# ledboard.net
KiCad netlist of a schematic drawn in EAGLE
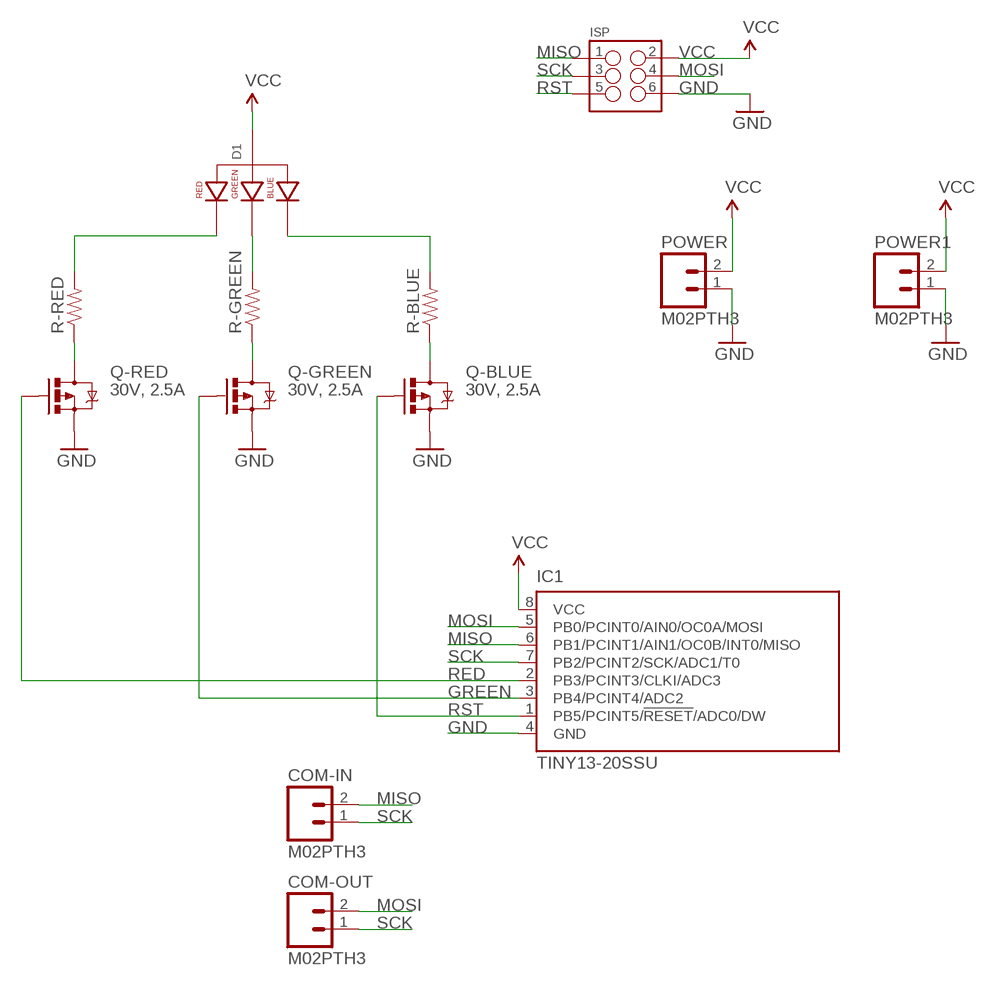
[diagram p0: schematic, sheet 1]

(export (version "E")
  (design (tool "Eeschema 10.0.6"))
  (components
    (comp (ref "COM-IN")
      (value "M02PTH3")
      (footprint "eagle-import:1X02_LONGPADS")
      (libsource (lib "eagle-import") (part "M02PTH3"))
    )
    (comp (ref "COM-OUT")
      (value "M02PTH3")
      (footprint "eagle-import:1X02_LONGPADS")
      (libsource (lib "eagle-import") (part "M02PTH3"))
    )
    (comp (ref "D1")
      (value "LED-RGB-CA-THRUCLEAR")
      (footprint "eagle-import:LED-RGB-THRU")
      (libsource (lib "eagle-import") (part "LED-RGB-CA-THRUCLEAR"))
    )
    (comp (ref "IC1")
      (value "TINY13-20SSU")
      (footprint "eagle-import:8S1")
      (fields (field (name "MPN") "ATTINY13-20SSU"))
      (libsource (lib "eagle-import") (part "TINY13SSU-20"))
    )
    (comp (ref "ISP")
      (value "M03X22X3_SILK_SM")
      (footprint "eagle-import:2X3")
      (libsource (lib "eagle-import") (part "M03X22X3_SILK_SM"))
    )
    (comp (ref "POWER")
      (value "M02PTH3")
      (footprint "eagle-import:1X02_LONGPADS")
      (libsource (lib "eagle-import") (part "M02PTH3"))
    )
    (comp (ref "POWER1")
      (value "M02PTH3")
      (footprint "eagle-import:1X02_LONGPADS")
      (libsource (lib "eagle-import") (part "M02PTH3"))
    )
    (comp (ref "Q-BLUE")
      (value "30V, 2.5A")
      (footprint "eagle-import:SOT23-3")
      (libsource (lib "eagle-import") (part "MOSFET-PCHANNELDMG2307L"))
    )
    (comp (ref "Q-GREEN")
      (value "30V, 2.5A")
      (footprint "eagle-import:SOT23-3")
      (libsource (lib "eagle-import") (part "MOSFET-PCHANNELDMG2307L"))
    )
    (comp (ref "Q-RED")
      (value "30V, 2.5A")
      (footprint "eagle-import:SOT23-3")
      (libsource (lib "eagle-import") (part "MOSFET-PCHANNELDMG2307L"))
    )
    (comp (ref "R-BLUE")
      (value "RESISTOR0603")
      (footprint "eagle-import:0603-RES")
      (libsource (lib "eagle-import") (part "RESISTOR0603"))
    )
    (comp (ref "R-GREEN")
      (value "RESISTOR0603")
      (footprint "eagle-import:0603-RES")
      (libsource (lib "eagle-import") (part "RESISTOR0603"))
    )
    (comp (ref "R-RED")
      (value "RESISTOR0603")
      (footprint "eagle-import:0603-RES")
      (libsource (lib "eagle-import") (part "RESISTOR0603"))
    )
  )
  (nets
    (net (code "1") (name "/GREEN") (class "Default")
      (node (ref "IC1") (pin "3") (pinfunction "PB4/PCINT4/ADC2_3") (pintype "bidirectional"))
      (node (ref "Q-GREEN") (pin "1") (pinfunction "G_1") (pintype "passive"))
    )
    (net (code "2") (name "/MISO") (class "Default")
      (node (ref "COM-IN") (pin "2") (pinfunction "2_2") (pintype "passive"))
      (node (ref "IC1") (pin "6") (pinfunction "PB1/PCINT1/AIN1/OC0B/INT0/MISO_6") (pintype "bidirectional"))
      (node (ref "ISP") (pin "1") (pinfunction "1_1") (pintype "bidirectional"))
    )
    (net (code "3") (name "/MOSI") (class "Default")
      (node (ref "COM-OUT") (pin "2") (pinfunction "2_2") (pintype "passive"))
      (node (ref "IC1") (pin "5") (pinfunction "PB0/PCINT0/AIN0/OC0A/MOSI_5") (pintype "bidirectional"))
      (node (ref "ISP") (pin "4") (pinfunction "4_4") (pintype "bidirectional"))
    )
    (net (code "4") (name "/RED") (class "Default")
      (node (ref "IC1") (pin "2") (pinfunction "PB3/PCINT3/CLKI/ADC3_2") (pintype "bidirectional"))
      (node (ref "Q-RED") (pin "1") (pinfunction "G_1") (pintype "passive"))
    )
    (net (code "5") (name "/RST") (class "Default")
      (node (ref "IC1") (pin "1") (pinfunction "PB5/PCINT5/~{RESET}/ADC0/DW_1") (pintype "bidirectional"))
      (node (ref "ISP") (pin "5") (pinfunction "5_5") (pintype "bidirectional"))
      (node (ref "Q-BLUE") (pin "1") (pinfunction "G_1") (pintype "passive"))
    )
    (net (code "6") (name "/SCK") (class "Default")
      (node (ref "COM-IN") (pin "1") (pinfunction "1_1") (pintype "passive"))
      (node (ref "COM-OUT") (pin "1") (pinfunction "1_1") (pintype "passive"))
      (node (ref "IC1") (pin "7") (pinfunction "PB2/PCINT2/SCK/ADC1/T0_7") (pintype "bidirectional"))
      (node (ref "ISP") (pin "3") (pinfunction "3_3") (pintype "bidirectional"))
    )
    (net (code "7") (name "GND") (class "Default")
      (node (ref "IC1") (pin "4") (pinfunction "GND_4") (pintype "power_in"))
      (node (ref "ISP") (pin "6") (pinfunction "6_6") (pintype "bidirectional"))
      (node (ref "POWER") (pin "1") (pinfunction "1_1") (pintype "passive"))
      (node (ref "POWER1") (pin "1") (pinfunction "1_1") (pintype "passive"))
      (node (ref "Q-BLUE") (pin "2") (pinfunction "S_2") (pintype "passive"))
      (node (ref "Q-GREEN") (pin "2") (pinfunction "S_2") (pintype "passive"))
      (node (ref "Q-RED") (pin "2") (pinfunction "S_2") (pintype "passive"))
    )
    (net (code "8") (name "Net-(D1-BLUE_CATHODE)") (class "Default")
      (node (ref "D1") (pin "4") (pinfunction "BLUE_CATHODE_4") (pintype "bidirectional"))
      (node (ref "R-BLUE") (pin "2") (pinfunction "2_2") (pintype "passive"))
    )
    (net (code "9") (name "Net-(D1-GREEN_CATHODE)") (class "Default")
      (node (ref "D1") (pin "3") (pinfunction "GREEN_CATHODE_3") (pintype "bidirectional"))
      (node (ref "R-GREEN") (pin "2") (pinfunction "2_2") (pintype "passive"))
    )
    (net (code "10") (name "Net-(D1-RED_CATHODE)") (class "Default")
      (node (ref "D1") (pin "1") (pinfunction "RED_CATHODE_1") (pintype "bidirectional"))
      (node (ref "R-RED") (pin "2") (pinfunction "2_2") (pintype "passive"))
    )
    (net (code "11") (name "Net-(Q-BLUE-D)") (class "Default")
      (node (ref "Q-BLUE") (pin "3") (pinfunction "D_3") (pintype "passive"))
      (node (ref "R-BLUE") (pin "1") (pinfunction "1_1") (pintype "passive"))
    )
    (net (code "12") (name "Net-(Q-GREEN-D)") (class "Default")
      (node (ref "Q-GREEN") (pin "3") (pinfunction "D_3") (pintype "passive"))
      (node (ref "R-GREEN") (pin "1") (pinfunction "1_1") (pintype "passive"))
    )
    (net (code "13") (name "Net-(Q-RED-D)") (class "Default")
      (node (ref "Q-RED") (pin "3") (pinfunction "D_3") (pintype "passive"))
      (node (ref "R-RED") (pin "1") (pinfunction "1_1") (pintype "passive"))
    )
    (net (code "14") (name "VCC") (class "Default")
      (node (ref "D1") (pin "2") (pinfunction "ANODE_2") (pintype "bidirectional"))
      (node (ref "IC1") (pin "8") (pinfunction "VCC_8") (pintype "power_in"))
      (node (ref "ISP") (pin "2") (pinfunction "2_2") (pintype "bidirectional"))
      (node (ref "POWER") (pin "2") (pinfunction "2_2") (pintype "passive"))
      (node (ref "POWER1") (pin "2") (pinfunction "2_2") (pintype "passive"))
    )
  )
)
